# HW1_NathanDonaldson_U0632803.net
KiCad netlist of a schematic drawn in EAGLE
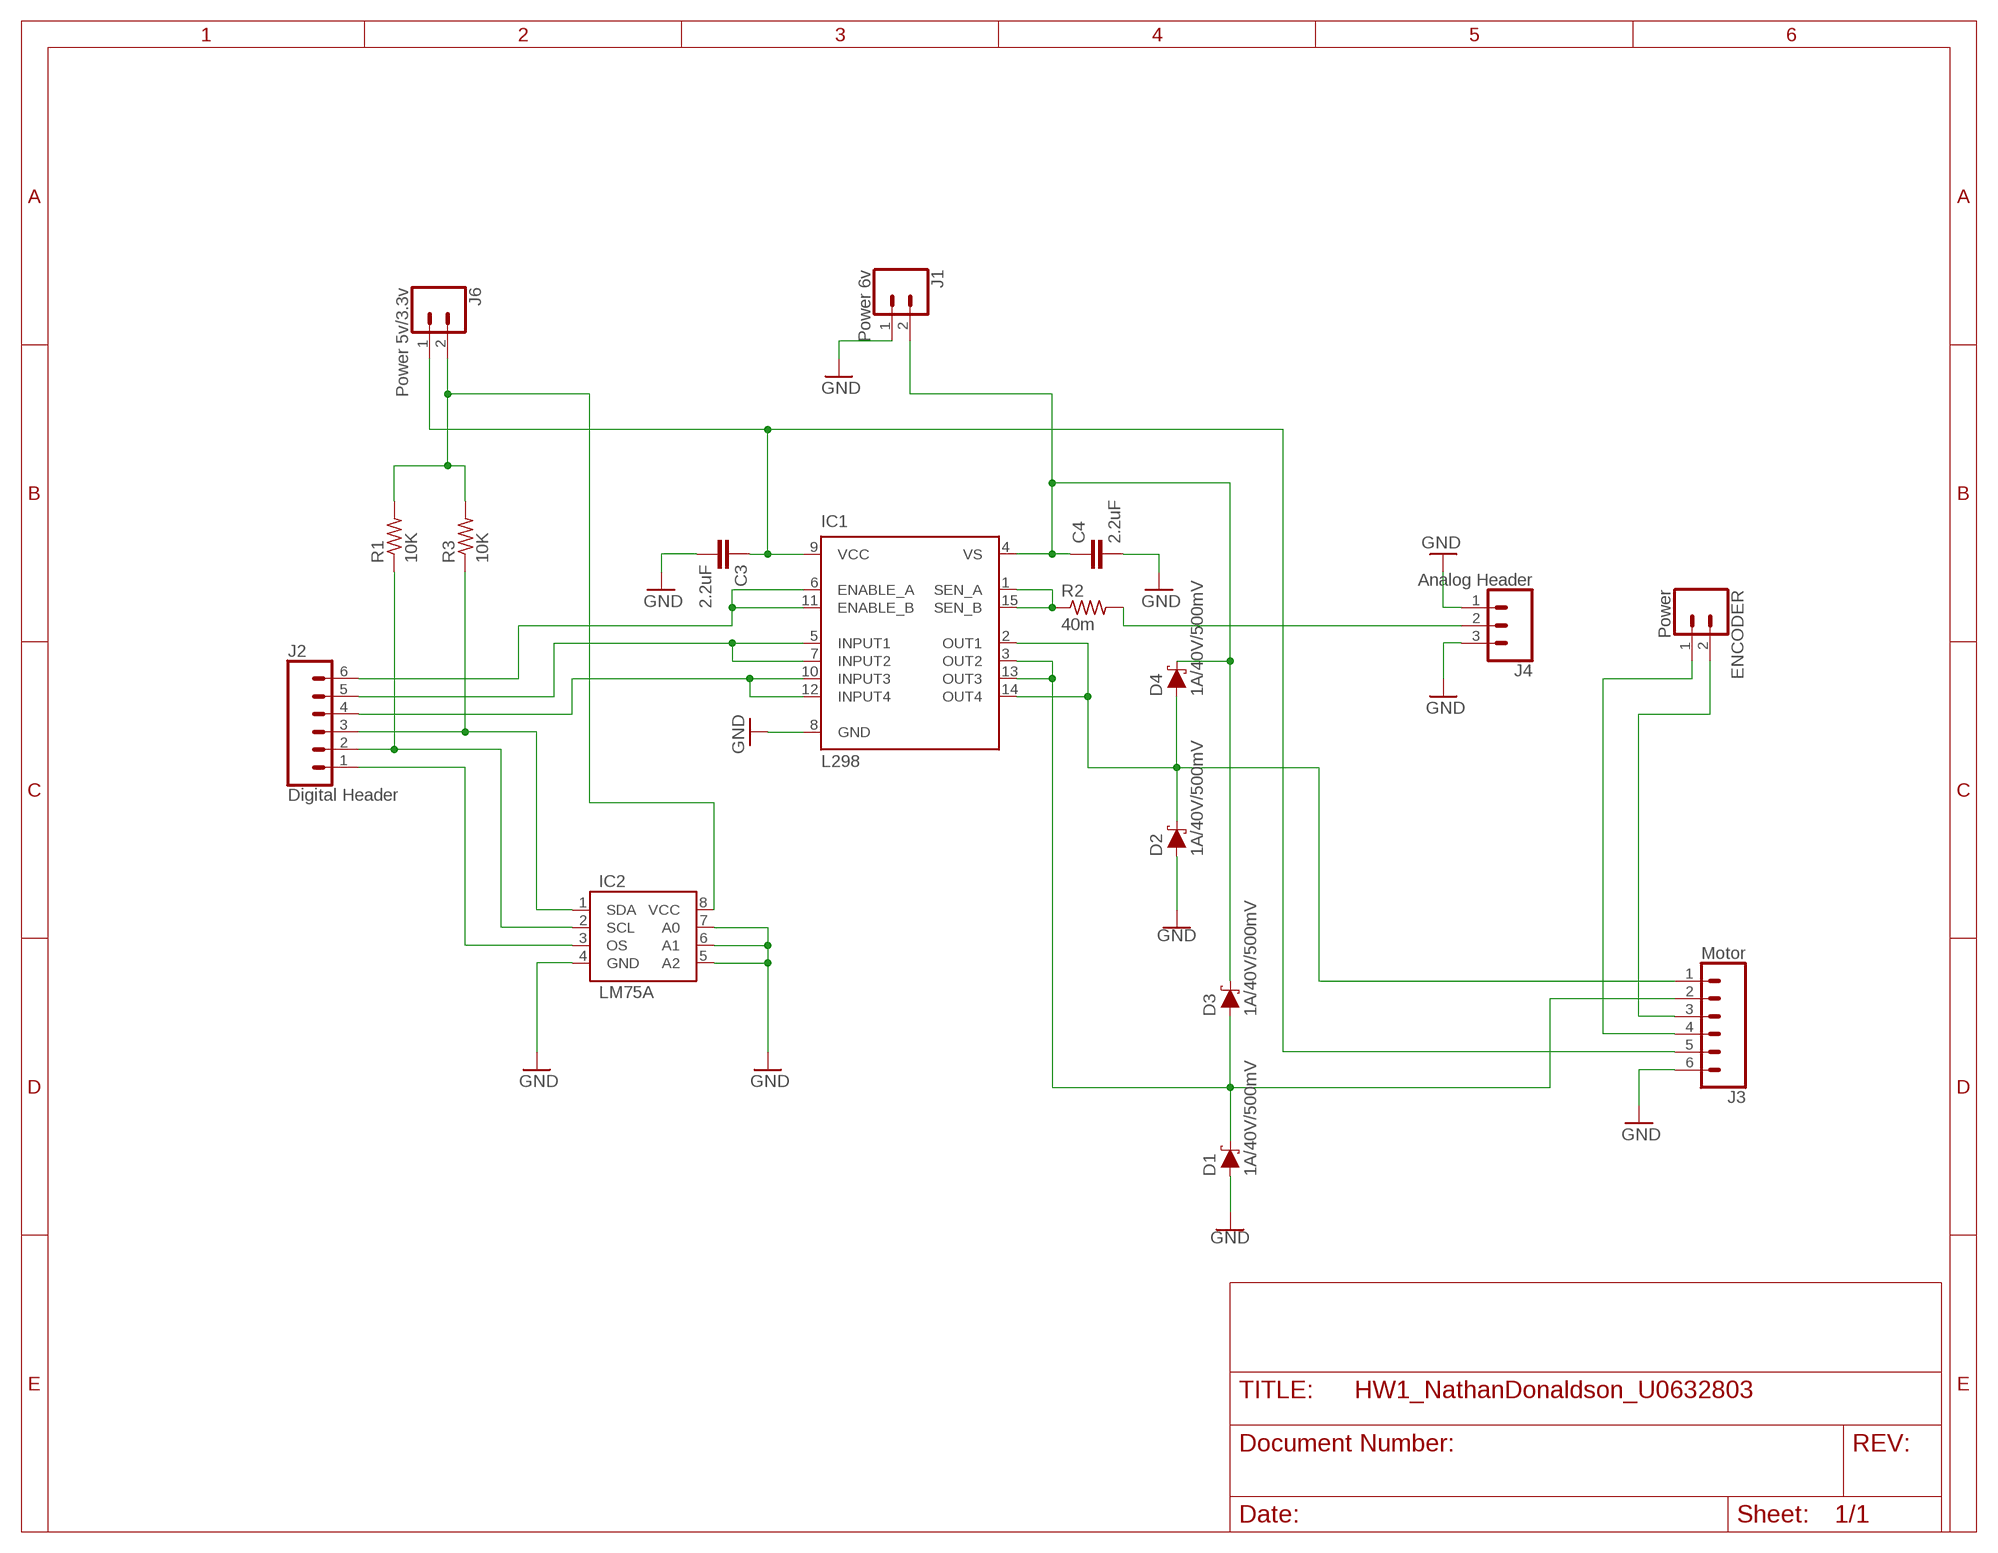
[diagram p0: schematic, sheet 1]

(export (version "E")
  (design (tool "Eeschema 10.0.6"))
  (components
    (comp (ref "C3")
      (value "2.2uF")
      (footprint "eagle-import:1206")
      (libsource (lib "eagle-import") (part "2.2UF-CERCAP-10009"))
    )
    (comp (ref "C4")
      (value "2.2uF")
      (footprint "eagle-import:1206")
      (libsource (lib "eagle-import") (part "2.2UF-CERCAP-10009"))
    )
    (comp (ref "D1")
      (value "1A/40V/500mV")
      (footprint "eagle-import:SMA-DIODE")
      (libsource (lib "eagle-import") (part "DIODE-SCHOTTKY-SS14"))
    )
    (comp (ref "D2")
      (value "1A/40V/500mV")
      (footprint "eagle-import:SMA-DIODE")
      (libsource (lib "eagle-import") (part "DIODE-SCHOTTKY-SS14"))
    )
    (comp (ref "D3")
      (value "1A/40V/500mV")
      (footprint "eagle-import:SMA-DIODE")
      (libsource (lib "eagle-import") (part "DIODE-SCHOTTKY-SS14"))
    )
    (comp (ref "D4")
      (value "1A/40V/500mV")
      (footprint "eagle-import:SMA-DIODE")
      (libsource (lib "eagle-import") (part "DIODE-SCHOTTKY-SS14"))
    )
    (comp (ref "ENCODER")
      (value "Power")
      (footprint "eagle-import:1X02")
      (libsource (lib "eagle-import") (part "CONN_02"))
    )
    (comp (ref "IC1")
      (value "L298")
      (footprint "eagle-import:MULTIWATT-15")
      (fields (field (name "MPN") "L298N"))
      (libsource (lib "eagle-import") (part "L298"))
    )
    (comp (ref "IC2")
      (value "LM75A")
      (footprint "eagle-import:SO8")
      (libsource (lib "eagle-import") (part "LM75A"))
    )
    (comp (ref "J1")
      (value "Power 6v")
      (footprint "eagle-import:1X02")
      (libsource (lib "eagle-import") (part "CONN_02"))
    )
    (comp (ref "J2")
      (value "Digital Header")
      (footprint "eagle-import:1X06_LOCK")
      (libsource (lib "eagle-import") (part "CONN_06LOCK"))
    )
    (comp (ref "J3")
      (value "Motor")
      (footprint "eagle-import:1X06_LOCK")
      (libsource (lib "eagle-import") (part "CONN_06LOCK"))
    )
    (comp (ref "J4")
      (value "Analog Header")
      (footprint "eagle-import:1X03")
      (libsource (lib "eagle-import") (part "CONN_03"))
    )
    (comp (ref "J6")
      (value "Power 5v/3.3v")
      (footprint "eagle-import:1X02")
      (libsource (lib "eagle-import") (part "CONN_02"))
    )
    (comp (ref "R1")
      (value "10K")
      (footprint "eagle-import:R1206")
      (libsource (lib "eagle-import") (part "R-US_R1206"))
    )
    (comp (ref "R2")
      (value "40m")
      (footprint "eagle-import:R1206")
      (libsource (lib "eagle-import") (part "R-US_R1206"))
    )
    (comp (ref "R3")
      (value "10K")
      (footprint "eagle-import:R1206")
      (libsource (lib "eagle-import") (part "R-US_R1206"))
    )
  )
  (nets
    (net (code "1") (name "GND") (class "Default")
      (node (ref "C3") (pin "2") (pinfunction "2_2") (pintype "passive"))
      (node (ref "C4") (pin "2") (pinfunction "2_2") (pintype "passive"))
      (node (ref "D1") (pin "A") (pinfunction "A_A") (pintype "passive"))
      (node (ref "D2") (pin "A") (pinfunction "A_A") (pintype "passive"))
      (node (ref "IC1") (pin "8") (pinfunction "GND_8") (pintype "power_in"))
      (node (ref "IC2") (pin "4") (pinfunction "GND_4") (pintype "bidirectional"))
      (node (ref "IC2") (pin "5") (pinfunction "A2_5") (pintype "bidirectional"))
      (node (ref "IC2") (pin "6") (pinfunction "A1_6") (pintype "bidirectional"))
      (node (ref "IC2") (pin "7") (pinfunction "A0_7") (pintype "bidirectional"))
      (node (ref "J1") (pin "1") (pinfunction "1_1") (pintype "passive"))
      (node (ref "J3") (pin "6") (pinfunction "6_6") (pintype "passive"))
      (node (ref "J4") (pin "1") (pinfunction "1_1") (pintype "passive"))
      (node (ref "J4") (pin "3") (pinfunction "3_3") (pintype "passive"))
    )
    (net (code "2") (name "Net-(ENCODER-Pad1)") (class "Default")
      (node (ref "ENCODER") (pin "1") (pinfunction "1_1") (pintype "passive"))
      (node (ref "J3") (pin "4") (pinfunction "4_4") (pintype "passive"))
    )
    (net (code "3") (name "Net-(ENCODER-Pad2)") (class "Default")
      (node (ref "ENCODER") (pin "2") (pinfunction "2_2") (pintype "passive"))
      (node (ref "J3") (pin "3") (pinfunction "3_3") (pintype "passive"))
    )
    (net (code "4") (name "Net-(IC1-ENABLE_A)") (class "Default")
      (node (ref "IC1") (pin "11") (pinfunction "ENABLE_B_11") (pintype "input"))
      (node (ref "IC1") (pin "6") (pinfunction "ENABLE_A_6") (pintype "input"))
      (node (ref "J2") (pin "6") (pinfunction "6_6") (pintype "passive"))
    )
    (net (code "5") (name "Net-(IC1-INPUT1)") (class "Default")
      (node (ref "IC1") (pin "5") (pinfunction "INPUT1_5") (pintype "input"))
      (node (ref "IC1") (pin "7") (pinfunction "INPUT2_7") (pintype "input"))
      (node (ref "J2") (pin "5") (pinfunction "5_5") (pintype "passive"))
    )
    (net (code "6") (name "Net-(IC1-INPUT3)") (class "Default")
      (node (ref "IC1") (pin "10") (pinfunction "INPUT3_10") (pintype "input"))
      (node (ref "IC1") (pin "12") (pinfunction "INPUT4_12") (pintype "input"))
      (node (ref "J2") (pin "4") (pinfunction "4_4") (pintype "passive"))
    )
    (net (code "7") (name "Net-(IC1-OUT1)") (class "Default")
      (node (ref "D2") (pin "C") (pinfunction "C_C") (pintype "passive"))
      (node (ref "D4") (pin "A") (pinfunction "A_A") (pintype "passive"))
      (node (ref "IC1") (pin "14") (pinfunction "OUT4_14") (pintype "output"))
      (node (ref "IC1") (pin "2") (pinfunction "OUT1_2") (pintype "output"))
      (node (ref "J3") (pin "1") (pinfunction "1_1") (pintype "passive"))
    )
    (net (code "8") (name "Net-(IC1-OUT2)") (class "Default")
      (node (ref "D1") (pin "C") (pinfunction "C_C") (pintype "passive"))
      (node (ref "D3") (pin "A") (pinfunction "A_A") (pintype "passive"))
      (node (ref "IC1") (pin "13") (pinfunction "OUT3_13") (pintype "output"))
      (node (ref "IC1") (pin "3") (pinfunction "OUT2_3") (pintype "output"))
      (node (ref "J3") (pin "2") (pinfunction "2_2") (pintype "passive"))
    )
    (net (code "9") (name "Net-(IC1-SEN_A)") (class "Default")
      (node (ref "IC1") (pin "1") (pinfunction "SEN_A_1") (pintype "input"))
      (node (ref "IC1") (pin "15") (pinfunction "SEN_B_15") (pintype "input"))
      (node (ref "R2") (pin "1") (pinfunction "1_1") (pintype "passive"))
    )
    (net (code "10") (name "Net-(IC1-VCC)") (class "Default")
      (node (ref "C3") (pin "1") (pinfunction "1_1") (pintype "passive"))
      (node (ref "IC1") (pin "9") (pinfunction "VCC_9") (pintype "power_in"))
      (node (ref "J3") (pin "5") (pinfunction "5_5") (pintype "passive"))
      (node (ref "J6") (pin "1") (pinfunction "1_1") (pintype "passive"))
    )
    (net (code "11") (name "Net-(IC1-VS)") (class "Default")
      (node (ref "C4") (pin "1") (pinfunction "1_1") (pintype "passive"))
      (node (ref "D3") (pin "C") (pinfunction "C_C") (pintype "passive"))
      (node (ref "D4") (pin "C") (pinfunction "C_C") (pintype "passive"))
      (node (ref "IC1") (pin "4") (pinfunction "VS_4") (pintype "power_in"))
      (node (ref "J1") (pin "2") (pinfunction "2_2") (pintype "passive"))
    )
    (net (code "12") (name "Net-(IC2-OS)") (class "Default")
      (node (ref "IC2") (pin "3") (pinfunction "OS_3") (pintype "bidirectional"))
      (node (ref "J2") (pin "1") (pinfunction "1_1") (pintype "passive"))
    )
    (net (code "13") (name "Net-(IC2-SCL)") (class "Default")
      (node (ref "IC2") (pin "2") (pinfunction "SCL_2") (pintype "bidirectional"))
      (node (ref "J2") (pin "2") (pinfunction "2_2") (pintype "passive"))
      (node (ref "R1") (pin "1") (pinfunction "1_1") (pintype "passive"))
    )
    (net (code "14") (name "Net-(IC2-SDA)") (class "Default")
      (node (ref "IC2") (pin "1") (pinfunction "SDA_1") (pintype "bidirectional"))
      (node (ref "J2") (pin "3") (pinfunction "3_3") (pintype "passive"))
      (node (ref "R3") (pin "1") (pinfunction "1_1") (pintype "passive"))
    )
    (net (code "15") (name "Net-(IC2-VCC)") (class "Default")
      (node (ref "IC2") (pin "8") (pinfunction "VCC_8") (pintype "bidirectional"))
      (node (ref "J6") (pin "2") (pinfunction "2_2") (pintype "passive"))
      (node (ref "R1") (pin "2") (pinfunction "2_2") (pintype "passive"))
      (node (ref "R3") (pin "2") (pinfunction "2_2") (pintype "passive"))
    )
    (net (code "16") (name "Net-(J4-Pad2)") (class "Default")
      (node (ref "J4") (pin "2") (pinfunction "2_2") (pintype "passive"))
      (node (ref "R2") (pin "2") (pinfunction "2_2") (pintype "passive"))
    )
  )
)
